# Arduino-Pro-Mini.net
KiCad netlist of a schematic drawn in Altium Designer
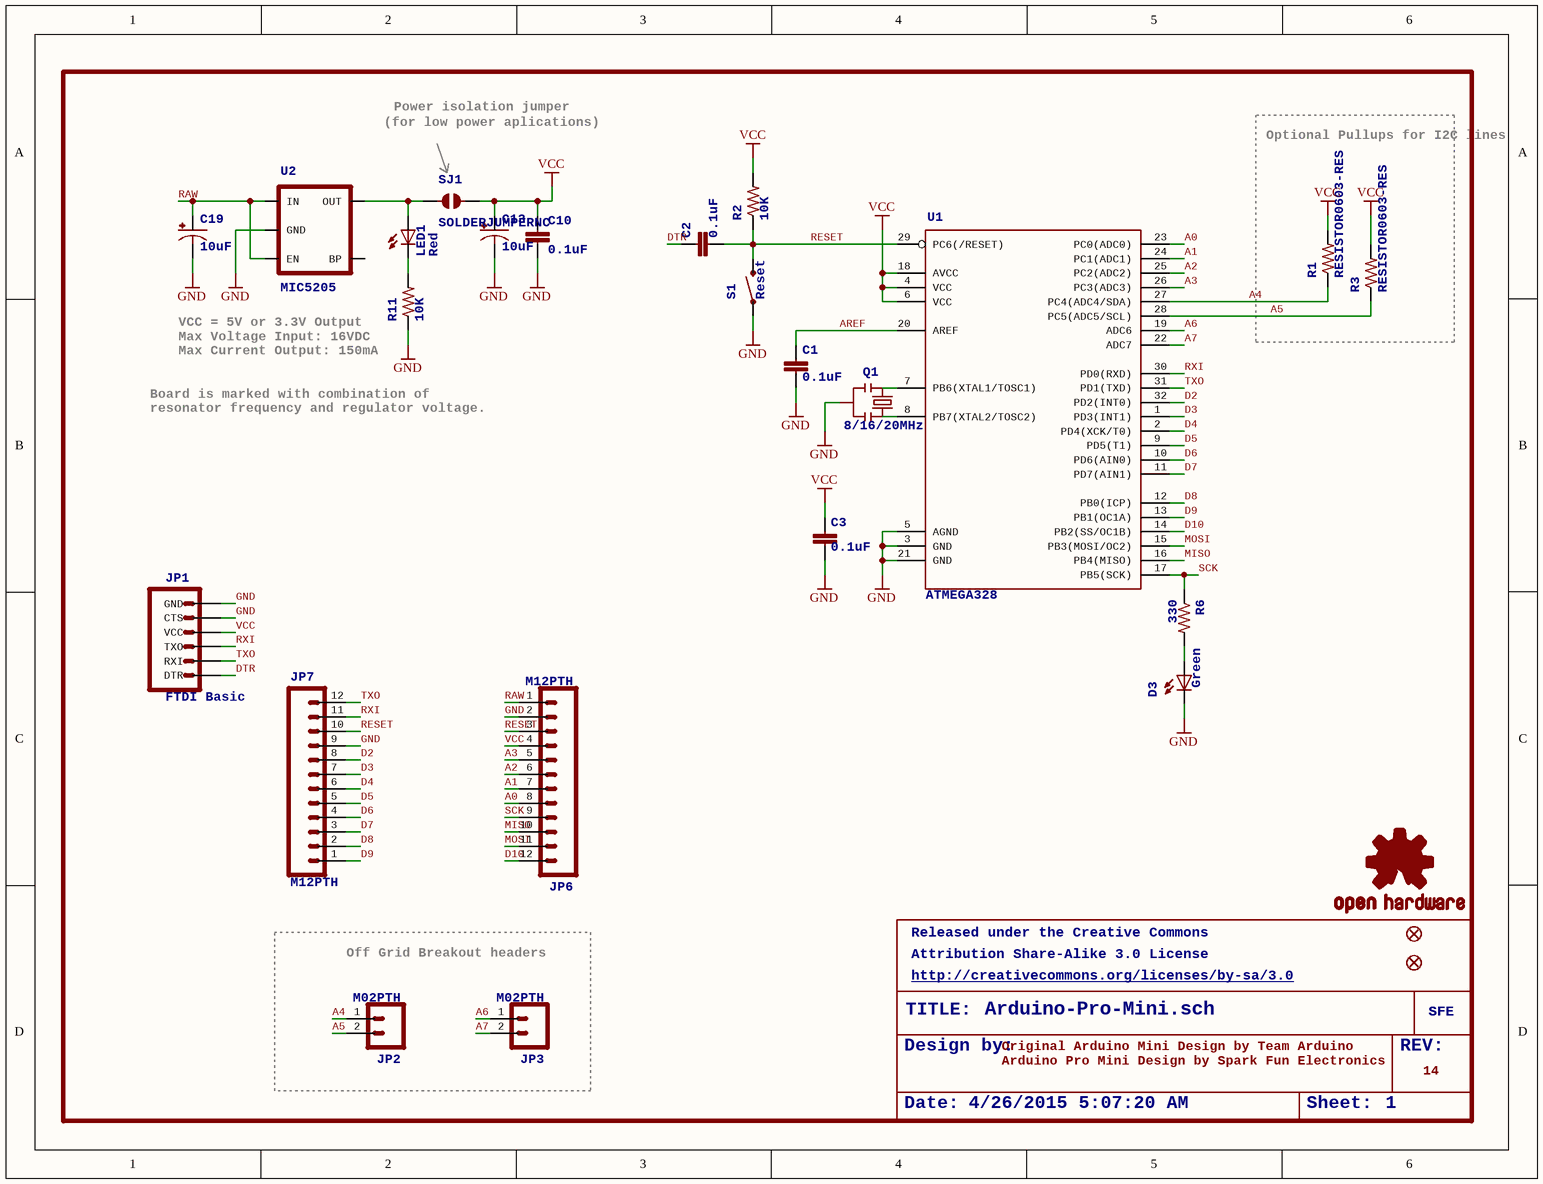
[diagram p0: Arduino-Pro-Mini.SchDoc]

(export (version "E")
  (design (tool "Eeschema 10.0.6"))
  (components
    (comp (ref "C1")
      (value "0.1uF")
      (footprint "0603-CAP")
      (description "<b>Capacitor</b>\nStandard 0603 ceramic capacitor, and 0.1\" leaded capacitor.")
      (libsource (lib "") (part "CAP0603-CAP_1"))
    )
    (comp (ref "C2")
      (value "0.1uF")
      (footprint "0603-CAP")
      (description "<b>Capacitor</b>\nStandard 0603 ceramic capacitor, and 0.1\" leaded capacitor.")
      (libsource (lib "SparkFun") (part "CAP0603-CAP"))
    )
    (comp (ref "C3")
      (value "0.1uF")
      (footprint "0603-CAP")
      (description "<b>Capacitor</b>\nStandard 0603 ceramic capacitor, and 0.1\" leaded capacitor.")
      (libsource (lib "") (part "CAP0603-CAP_1"))
    )
    (comp (ref "C10")
      (value "0.1uF")
      (footprint "0603-CAP")
      (description "<b>Capacitor</b>\nStandard 0603 ceramic capacitor, and 0.1\" leaded capacitor.")
      (libsource (lib "") (part "CAP0603-CAP_2"))
    )
    (comp (ref "C13") (value "10uF") (footprint "EIA3216") (libsource (lib "SparkFun") (part "CAP_POL1206")))
    (comp (ref "C19") (value "10uF") (footprint "EIA3216") (libsource (lib "SparkFun") (part "CAP_POL1206")))
    (comp (ref "D3") (value "Green") (footprint "0603-LED-ALT1") (libsource (lib "Testing") (part "LED")))
    (comp (ref "JP1")
      (value "FTDI Basic")
      (footprint "1X06")
      (libsource (lib "SparkFun") (part "ARDUINO_SERIAL_PROGRAMPTH"))
    )
    (comp (ref "JP2") (value "M02PTH") (footprint "1X02") (libsource (lib "SparkFun") (part "M02PTH")))
    (comp (ref "JP3") (value "M02PTH") (footprint "1X02") (libsource (lib "SparkFun") (part "M02PTH")))
    (comp (ref "JP5")
      (value "FIDUCIALUFIDUCIAL")
      (footprint "MICRO-FIDUCIAL")
      (description "<b>Fiducial Alignment Points</b>\nVarious fiducial points for machine vision alignment.")
      (libsource (lib "SparkFun") (part "FIDUCIALUFIDUCIAL"))
    )
    (comp (ref "JP6") (value "M12PTH") (footprint "1X12") (libsource (lib "SparkFun") (part "M12PTH")))
    (comp (ref "JP7") (value "M12PTH") (footprint "1X12") (libsource (lib "SparkFun") (part "M12PTH")))
    (comp (ref "JP8")
      (value "FIDUCIALUFIDUCIAL")
      (footprint "MICRO-FIDUCIAL")
      (description "<b>Fiducial Alignment Points</b>\nVarious fiducial points for machine vision alignment.")
      (libsource (lib "SparkFun") (part "FIDUCIALUFIDUCIAL"))
    )
    (comp (ref "LED1") (value "Red") (footprint "0603-LED-ALT1") (libsource (lib "Testing") (part "LED")))
    (comp (ref "Q1")
      (value "8/16/20MHz")
      (footprint "RESONATOR-SMD-1:1")
      (libsource (lib "Testing") (part "RESONATOR1{colon}1"))
    )
    (comp (ref "R1")
      (value "RESISTOR0603-RES")
      (footprint "0603-RES")
      (description "<b>Resistor</b>\nBasic schematic elements and footprints for 0603, 1206, and PTH resistors.")
      (libsource (lib "SparkFun") (part "RESISTOR0603-RES"))
    )
    (comp (ref "R2")
      (value "10K")
      (footprint "0603-RES")
      (description "<b>Resistor</b>\nBasic schematic elements and footprints for 0603, 1206, and PTH resistors.")
      (libsource (lib "SparkFun") (part "RESISTOR0603-RES"))
    )
    (comp (ref "R3")
      (value "RESISTOR0603-RES")
      (footprint "0603-RES")
      (description "<b>Resistor</b>\nBasic schematic elements and footprints for 0603, 1206, and PTH resistors.")
      (libsource (lib "SparkFun") (part "RESISTOR0603-RES"))
    )
    (comp (ref "R6")
      (value "330")
      (footprint "0603-RES")
      (description "<b>Resistor</b>\nBasic schematic elements and footprints for 0603, 1206, and PTH resistors.")
      (libsource (lib "SparkFun") (part "RESISTOR0603-RES"))
    )
    (comp (ref "R11")
      (value "10K")
      (footprint "0603-RES")
      (description "<b>Resistor</b>\nBasic schematic elements and footprints for 0603, 1206, and PTH resistors.")
      (libsource (lib "SparkFun") (part "RESISTOR0603-RES"))
    )
    (comp (ref "S1")
      (value "Reset")
      (footprint "TACTILE-SWITCH-SMD-ALT01")
      (description "Various NO switches- pushbuttons, reed, etc")
      (libsource (lib "Testing") (part "SWITCH-MOMENTARY-2SMD-ALT01"))
    )
    (comp (ref "SJ1")
      (value "SOLDERJUMPERNC")
      (footprint "SJ_2S")
      (libsource (lib "SparkFun-Passives") (part "SOLDERJUMPERNC"))
    )
    (comp (ref "U$1")
      (value "LOGO-SFESK")
      (footprint "SFE-LOGO-FLAME")
      (description "<b>Spark Fun Electronics PCB Logo</b>\nThis is the standard Spark Fun Electronics PCB logo.")
      (fields (field (name "SFE") "SFE"))
      (libsource (lib "SparkFun") (part "LOGO-SFESK"))
    )
    (comp (ref "U$3")
      (value "OSHW-LOGOS")
      (footprint "OSHW-LOGO-S")
      (libsource (lib "SparkFun") (part "OSHW-LOGOS"))
    )
    (comp (ref "U$11")
      (value "LOGO-SFENEW")
      (footprint "SFE-NEW-WEBLOGO")
      (description "<b>Spark Fun Electronics PCB Logo</b>\nThis is the standard Spark Fun Electronics PCB logo.")
      (fields (field (name "SFE") "SFE"))
      (libsource (lib "SparkFun") (part "LOGO-SFENEW"))
    )
    (comp (ref "U1")
      (value "ATMEGA328")
      (footprint "TQFP32-08")
      (libsource (lib "SparkFun") (part "ATMEGA168"))
    )
    (comp (ref "U2")
      (value "MIC5205")
      (footprint "SOT23-5")
      (libsource (lib "SparkFun") (part "V_REG_LDOSMD"))
    )
  )
  (nets
    (net (code "1") (name "/A0") (class "Default")
      (node (ref "JP6") (pin "8") (pinfunction "8_8") (pintype "passive"))
      (node (ref "U1") (pin "23") (pinfunction "PC0(ADC0)_23") (pintype "passive"))
    )
    (net (code "2") (name "/A1") (class "Default")
      (node (ref "JP6") (pin "7") (pinfunction "7_7") (pintype "passive"))
      (node (ref "U1") (pin "24") (pinfunction "PC1(ADC1)_24") (pintype "passive"))
    )
    (net (code "3") (name "/A2") (class "Default")
      (node (ref "JP6") (pin "6") (pinfunction "6_6") (pintype "passive"))
      (node (ref "U1") (pin "25") (pinfunction "PC2(ADC2)_25") (pintype "passive"))
    )
    (net (code "4") (name "/A3") (class "Default")
      (node (ref "JP6") (pin "5") (pinfunction "5_5") (pintype "passive"))
      (node (ref "U1") (pin "26") (pinfunction "PC3(ADC3)_26") (pintype "passive"))
    )
    (net (code "5") (name "/A4") (class "Default")
      (node (ref "JP2") (pin "1") (pinfunction "1_1") (pintype "passive"))
      (node (ref "R1") (pin "1") (pinfunction "1_1") (pintype "passive"))
      (node (ref "U1") (pin "27") (pinfunction "PC4(ADC4/SDA)_27") (pintype "passive"))
    )
    (net (code "6") (name "/A5") (class "Default")
      (node (ref "JP2") (pin "2") (pinfunction "2_2") (pintype "passive"))
      (node (ref "R3") (pin "1") (pinfunction "1_1") (pintype "passive"))
      (node (ref "U1") (pin "28") (pinfunction "PC5(ADC5/SCL)_28") (pintype "passive"))
    )
    (net (code "7") (name "/A6") (class "Default")
      (node (ref "JP3") (pin "1") (pinfunction "1_1") (pintype "passive"))
      (node (ref "U1") (pin "19") (pinfunction "ADC6_19") (pintype "passive"))
    )
    (net (code "8") (name "/A7") (class "Default")
      (node (ref "JP3") (pin "2") (pinfunction "2_2") (pintype "passive"))
      (node (ref "U1") (pin "22") (pinfunction "ADC7_22") (pintype "passive"))
    )
    (net (code "9") (name "/AREF") (class "Default")
      (node (ref "C1") (pin "2") (pinfunction "2_2") (pintype "passive"))
      (node (ref "U1") (pin "20") (pinfunction "AREF_20") (pintype "passive"))
    )
    (net (code "10") (name "/D2") (class "Default")
      (node (ref "JP7") (pin "8") (pinfunction "8_8") (pintype "passive"))
      (node (ref "U1") (pin "32") (pinfunction "PD2(INT0)_32") (pintype "passive"))
    )
    (net (code "11") (name "/D3") (class "Default")
      (node (ref "JP7") (pin "7") (pinfunction "7_7") (pintype "passive"))
      (node (ref "U1") (pin "1") (pinfunction "PD3(INT1)_1") (pintype "passive"))
    )
    (net (code "12") (name "/D4") (class "Default")
      (node (ref "JP7") (pin "6") (pinfunction "6_6") (pintype "passive"))
      (node (ref "U1") (pin "2") (pinfunction "PD4(XCK/T0)_2") (pintype "passive"))
    )
    (net (code "13") (name "/D5") (class "Default")
      (node (ref "JP7") (pin "5") (pinfunction "5_5") (pintype "passive"))
      (node (ref "U1") (pin "9") (pinfunction "PD5(T1)_9") (pintype "passive"))
    )
    (net (code "14") (name "/D6") (class "Default")
      (node (ref "JP7") (pin "4") (pinfunction "4_4") (pintype "passive"))
      (node (ref "U1") (pin "10") (pinfunction "PD6(AIN0)_10") (pintype "passive"))
    )
    (net (code "15") (name "/D7") (class "Default")
      (node (ref "JP7") (pin "3") (pinfunction "3_3") (pintype "passive"))
      (node (ref "U1") (pin "11") (pinfunction "PD7(AIN1)_11") (pintype "passive"))
    )
    (net (code "16") (name "/D8") (class "Default")
      (node (ref "JP7") (pin "2") (pinfunction "2_2") (pintype "passive"))
      (node (ref "U1") (pin "12") (pinfunction "PB0(ICP)_12") (pintype "passive"))
    )
    (net (code "17") (name "/D9") (class "Default")
      (node (ref "JP7") (pin "1") (pinfunction "1_1") (pintype "passive"))
      (node (ref "U1") (pin "13") (pinfunction "PB1(OC1A)_13") (pintype "passive"))
    )
    (net (code "18") (name "/D10") (class "Default")
      (node (ref "JP6") (pin "12") (pinfunction "12_12") (pintype "passive"))
      (node (ref "U1") (pin "14") (pinfunction "PB2(SS/OC1B)_14") (pintype "passive"))
    )
    (net (code "19") (name "/DTR") (class "Default")
      (node (ref "C2") (pin "2") (pinfunction "2_2") (pintype "passive"))
      (node (ref "JP1") (pin "1") (pinfunction "DTR_1") (pintype "passive"))
    )
    (net (code "20") (name "/MISO") (class "Default")
      (node (ref "JP6") (pin "10") (pinfunction "10_10") (pintype "passive"))
      (node (ref "U1") (pin "16") (pinfunction "PB4(MISO)_16") (pintype "passive"))
    )
    (net (code "21") (name "/MOSI") (class "Default")
      (node (ref "JP6") (pin "11") (pinfunction "11_11") (pintype "passive"))
      (node (ref "U1") (pin "15") (pinfunction "PB3(MOSI/OC2)_15") (pintype "passive"))
    )
    (net (code "22") (name "/RAW") (class "Default")
      (node (ref "C19") (pin "A") (pinfunction "+_A") (pintype "passive"))
      (node (ref "JP6") (pin "1") (pinfunction "1_1") (pintype "passive"))
      (node (ref "U2") (pin "1") (pinfunction "IN_1") (pintype "passive"))
      (node (ref "U2") (pin "3") (pinfunction "EN_3") (pintype "passive"))
    )
    (net (code "23") (name "/RESET") (class "Default")
      (node (ref "C2") (pin "1") (pinfunction "1_1") (pintype "passive"))
      (node (ref "JP6") (pin "3") (pinfunction "3_3") (pintype "passive"))
      (node (ref "JP7") (pin "10") (pinfunction "10_10") (pintype "passive"))
      (node (ref "R2") (pin "1") (pinfunction "1_1") (pintype "passive"))
      (node (ref "S1") (pin "3_4") (pinfunction "2_3_4") (pintype "passive"))
      (node (ref "U1") (pin "29") (pinfunction "PC6(/RESET)_29") (pintype "passive"))
    )
    (net (code "24") (name "/RXI") (class "Default")
      (node (ref "JP1") (pin "3") (pinfunction "TXO_3") (pintype "passive"))
      (node (ref "JP7") (pin "11") (pinfunction "11_11") (pintype "passive"))
      (node (ref "U1") (pin "30") (pinfunction "PD0(RXD)_30") (pintype "passive"))
    )
    (net (code "25") (name "/SCK") (class "Default")
      (node (ref "JP6") (pin "9") (pinfunction "9_9") (pintype "passive"))
      (node (ref "R6") (pin "1") (pinfunction "1_1") (pintype "passive"))
      (node (ref "U1") (pin "17") (pinfunction "PB5(SCK)_17") (pintype "passive"))
    )
    (net (code "26") (name "/TXO") (class "Default")
      (node (ref "JP1") (pin "2") (pinfunction "RXI_2") (pintype "passive"))
      (node (ref "JP7") (pin "12") (pinfunction "12_12") (pintype "passive"))
      (node (ref "U1") (pin "31") (pinfunction "PD1(TXD)_31") (pintype "passive"))
    )
    (net (code "27") (name "GND") (class "Default")
      (node (ref "C1") (pin "1") (pinfunction "1_1") (pintype "passive"))
      (node (ref "C10") (pin "2") (pinfunction "2_2") (pintype "passive"))
      (node (ref "C13") (pin "C") (pinfunction "-_C") (pintype "passive"))
      (node (ref "C19") (pin "C") (pinfunction "-_C") (pintype "passive"))
      (node (ref "C3") (pin "1") (pinfunction "1_1") (pintype "passive"))
      (node (ref "D3") (pin "C") (pinfunction "C_C") (pintype "passive"))
      (node (ref "JP1") (pin "5") (pinfunction "CTS_5") (pintype "passive"))
      (node (ref "JP1") (pin "6") (pinfunction "GND_6") (pintype "passive"))
      (node (ref "JP6") (pin "2") (pinfunction "2_2") (pintype "passive"))
      (node (ref "JP7") (pin "9") (pinfunction "9_9") (pintype "passive"))
      (node (ref "Q1") (pin "2") (pinfunction "2_2") (pintype "passive"))
      (node (ref "R11") (pin "1") (pinfunction "1_1") (pintype "passive"))
      (node (ref "S1") (pin "1_2") (pinfunction "1_1_2") (pintype "passive"))
      (node (ref "U1") (pin "21") (pinfunction "GND_21") (pintype "passive"))
      (node (ref "U1") (pin "3") (pinfunction "GND_3") (pintype "passive"))
      (node (ref "U1") (pin "5") (pinfunction "AGND_5") (pintype "passive"))
      (node (ref "U2") (pin "2") (pinfunction "GND_2") (pintype "passive"))
    )
    (net (code "28") (name "Net-(D3-PadA)") (class "Default")
      (node (ref "D3") (pin "A") (pinfunction "A_A") (pintype "passive"))
      (node (ref "R6") (pin "2") (pinfunction "2_2") (pintype "passive"))
    )
    (net (code "29") (name "Net-(LED1-PadC)") (class "Default")
      (node (ref "LED1") (pin "C") (pinfunction "C_C") (pintype "passive"))
      (node (ref "R11") (pin "2") (pinfunction "2_2") (pintype "passive"))
    )
    (net (code "30") (name "Net-(U1-PB6(XTAL1{slash}TOSC1))") (class "Default")
      (node (ref "Q1") (pin "1") (pinfunction "1_1") (pintype "passive"))
      (node (ref "U1") (pin "7") (pinfunction "PB6(XTAL1/TOSC1)_7") (pintype "passive"))
    )
    (net (code "31") (name "Net-(U1-PB7(XTAL2{slash}TOSC2))") (class "Default")
      (node (ref "Q1") (pin "3") (pinfunction "3_3") (pintype "passive"))
      (node (ref "U1") (pin "8") (pinfunction "PB7(XTAL2/TOSC2)_8") (pintype "passive"))
    )
    (net (code "32") (name "Net-(U2-OUT)") (class "Default")
      (node (ref "LED1") (pin "A") (pinfunction "A_A") (pintype "passive"))
      (node (ref "SJ1") (pin "1") (pinfunction "1_1") (pintype "passive"))
      (node (ref "U2") (pin "5") (pinfunction "OUT_5") (pintype "passive"))
    )
    (net (code "33") (name "VCC") (class "Default")
      (node (ref "C10") (pin "1") (pinfunction "1_1") (pintype "passive"))
      (node (ref "C13") (pin "A") (pinfunction "+_A") (pintype "passive"))
      (node (ref "C3") (pin "2") (pinfunction "2_2") (pintype "passive"))
      (node (ref "JP1") (pin "4") (pinfunction "VCC_4") (pintype "passive"))
      (node (ref "JP6") (pin "4") (pinfunction "4_4") (pintype "passive"))
      (node (ref "R1") (pin "2") (pinfunction "2_2") (pintype "passive"))
      (node (ref "R2") (pin "2") (pinfunction "2_2") (pintype "passive"))
      (node (ref "R3") (pin "2") (pinfunction "2_2") (pintype "passive"))
      (node (ref "SJ1") (pin "2") (pinfunction "2_2") (pintype "passive"))
      (node (ref "U1") (pin "18") (pinfunction "AVCC_18") (pintype "passive"))
      (node (ref "U1") (pin "4") (pinfunction "VCC_4") (pintype "passive"))
      (node (ref "U1") (pin "6") (pinfunction "VCC_6") (pintype "passive"))
    )
    (net (code "34") (name "unconnected-(U2-BP-Pad4)") (class "Default")
      (node (ref "U2") (pin "4") (pinfunction "BP_4") (pintype "passive"))
    )
  )
)
